# Sheet1.net
KiCad netlist of a schematic drawn in Altium Designer
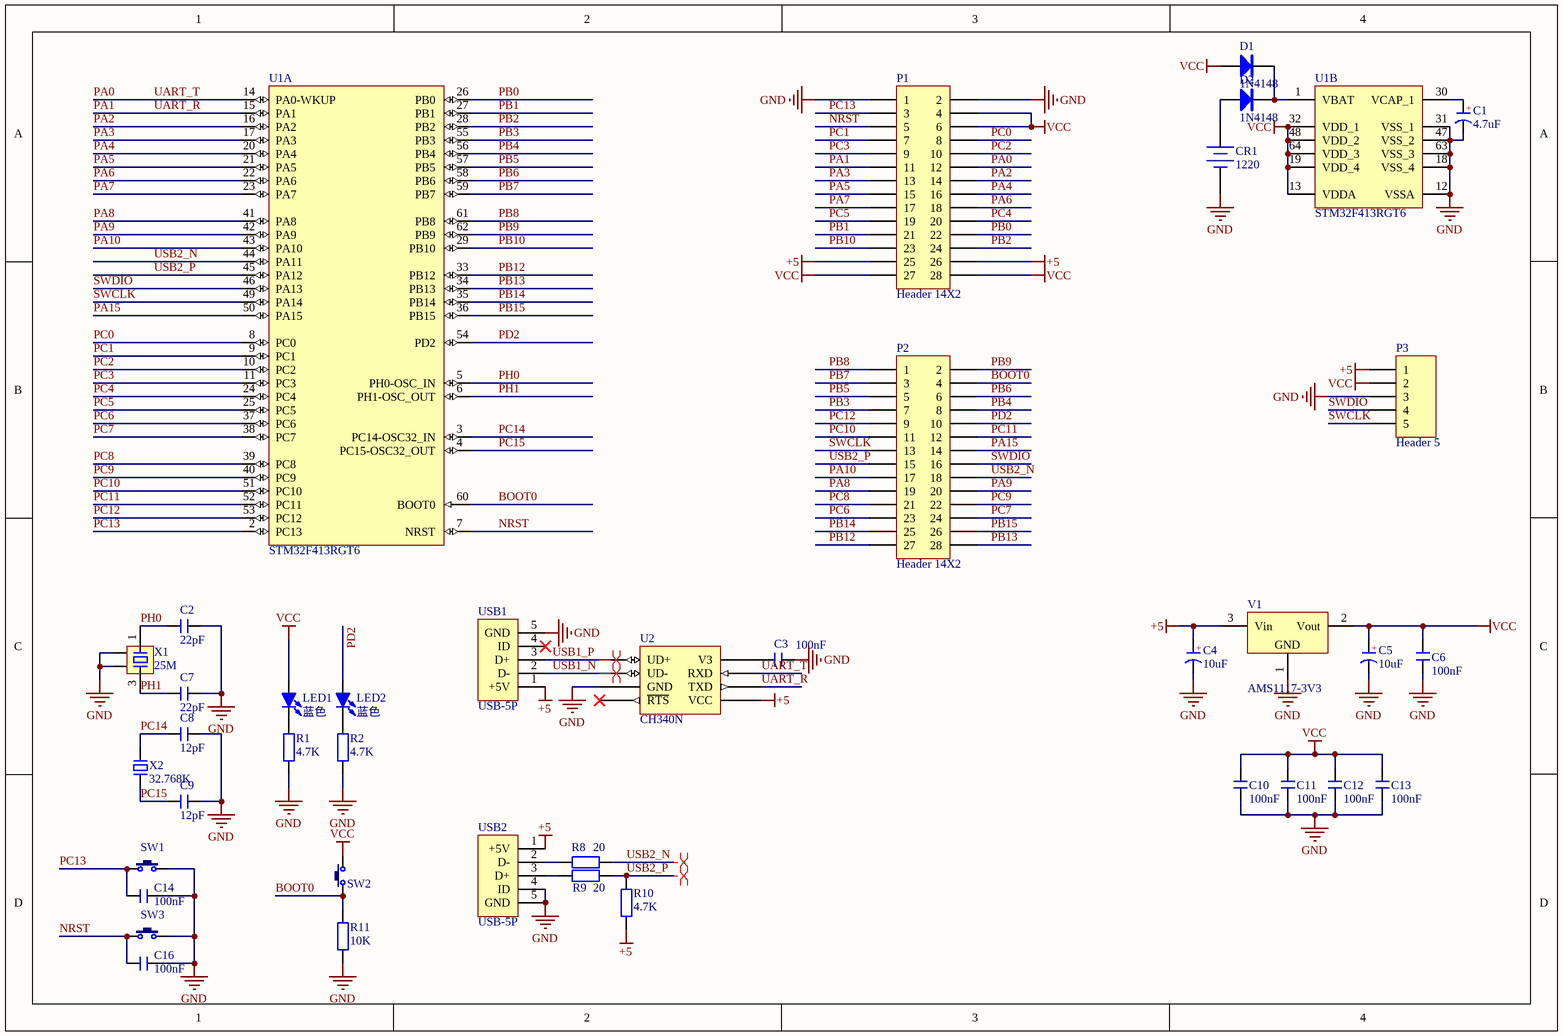
[diagram p0: Sheet1.SchDoc]

(export (version "E")
  (design (tool "Eeschema 10.0.6"))
  (components
    (comp (ref "C1")
      (value "4.7uF")
      (footprint "CD A(3216)")
      (description "贴片钽电容")
      (libsource (lib "Full") (part "CT"))
    )
    (comp (ref "C2")
      (value "22pF")
      (footprint "C 0603_L")
      (description "贴片电容")
      (libsource (lib "Full") (part "C"))
    )
    (comp (ref "C3")
      (value "100nF")
      (footprint "C 0603_L")
      (description "贴片电容")
      (libsource (lib "Full") (part "C"))
    )
    (comp (ref "C4")
      (value "10uF")
      (footprint "CD A(3216)")
      (description "贴片钽电容")
      (libsource (lib "Full") (part "CT"))
    )
    (comp (ref "C5")
      (value "10uF")
      (footprint "CD A(3216)")
      (description "贴片钽电容")
      (libsource (lib "Full") (part "CT"))
    )
    (comp (ref "C6")
      (value "100nF")
      (footprint "C 0603_L")
      (description "贴片电容")
      (libsource (lib "Full") (part "C"))
    )
    (comp (ref "C7")
      (value "22pF")
      (footprint "C 0603_L")
      (description "贴片电容")
      (libsource (lib "Full") (part "C"))
    )
    (comp (ref "C8")
      (value "12pF")
      (footprint "C 0603_L")
      (description "贴片电容")
      (libsource (lib "Full") (part "C"))
    )
    (comp (ref "C9")
      (value "12pF")
      (footprint "C 0603_L")
      (description "贴片电容")
      (libsource (lib "Full") (part "C"))
    )
    (comp (ref "C10")
      (value "100nF")
      (footprint "C 0603_L")
      (description "贴片电容")
      (libsource (lib "Full") (part "C"))
    )
    (comp (ref "C11")
      (value "100nF")
      (footprint "C 0603_L")
      (description "贴片电容")
      (libsource (lib "Full") (part "C"))
    )
    (comp (ref "C12")
      (value "100nF")
      (footprint "C 0603_L")
      (description "贴片电容")
      (libsource (lib "Full") (part "C"))
    )
    (comp (ref "C13")
      (value "100nF")
      (footprint "C 0603_L")
      (description "贴片电容")
      (libsource (lib "Full") (part "C"))
    )
    (comp (ref "C14")
      (value "100nF")
      (footprint "C 0603_L")
      (description "贴片电容")
      (libsource (lib "Full") (part "C"))
    )
    (comp (ref "C16")
      (value "100nF")
      (footprint "C 0603_L")
      (description "贴片电容")
      (libsource (lib "Full") (part "C"))
    )
    (comp (ref "CR1")
      (value "1220")
      (footprint "CR1220_B")
      (description "微型电池")
      (fields (field (name "版权归属") "封装库来自淘宝 ID：黄晶宝石"))
      (libsource (lib "Full") (part "CR-3V"))
    )
    (comp (ref "D1")
      (value "1N4148")
      (footprint "SOD-323")
      (description "开关二极管")
      (libsource (lib "Full") (part "1N4148"))
    )
    (comp (ref "D2")
      (value "1N4148")
      (footprint "SOD-323")
      (description "开关二极管")
      (libsource (lib "Full") (part "1N4148"))
    )
    (comp (ref "LED1")
      (value "蓝色")
      (footprint "LED 0805B")
      (description "贴片LED")
      (fields (field (name "版权归属") "封装库来自淘宝 ID：黄晶宝石"))
      (libsource (lib "Full") (part "LED-SMD"))
    )
    (comp (ref "LED2")
      (value "蓝色")
      (footprint "LED 0805B")
      (description "贴片LED")
      (fields (field (name "版权归属") "封装库来自淘宝 ID：黄晶宝石"))
      (libsource (lib "Full") (part "LED-SMD"))
    )
    (comp (ref "P1")
      (value "Header 14X2")
      (footprint "HDR2X14")
      (description "Header, 14-Pin, Dual row")
      (fields (field (name "PUBLISHER") "Altium Limited"))
      (libsource (lib "Miscellaneous Connectors") (part "Header 14X2"))
    )
    (comp (ref "P2")
      (value "Header 14X2")
      (footprint "HDR2X14")
      (description "Header, 14-Pin, Dual row")
      (fields (field (name "PUBLISHER") "Altium Limited"))
      (libsource (lib "Miscellaneous Connectors") (part "Header 14X2"))
    )
    (comp (ref "P3")
      (value "Header 5")
      (footprint "HDR1X5")
      (description "Header, 5-Pin")
      (fields (field (name "PUBLISHER") "Altium Limited"))
      (libsource (lib "Miscellaneous Connectors") (part "Header 5"))
    )
    (comp (ref "R1")
      (value "4.7K")
      (footprint "R 0603_L")
      (description "贴片电阻")
      (fields (field (name "版权归属") "来自淘宝 ID：黄晶宝石"))
      (libsource (lib "Full") (part "R"))
    )
    (comp (ref "R2")
      (value "4.7K")
      (footprint "R 0603_L")
      (description "贴片电阻")
      (fields (field (name "版权归属") "来自淘宝 ID：黄晶宝石"))
      (libsource (lib "Full") (part "R"))
    )
    (comp (ref "R8")
      (value "20")
      (footprint "R 0603_L")
      (description "贴片电阻")
      (fields (field (name "版权归属") "来自淘宝 ID：黄晶宝石"))
      (libsource (lib "Full") (part "R"))
    )
    (comp (ref "R9")
      (value "20")
      (footprint "R 0603_L")
      (description "贴片电阻")
      (fields (field (name "版权归属") "来自淘宝 ID：黄晶宝石"))
      (libsource (lib "Full") (part "R"))
    )
    (comp (ref "R10")
      (value "4.7K")
      (footprint "R 0603_L")
      (description "贴片电阻")
      (fields (field (name "版权归属") "来自淘宝 ID：黄晶宝石"))
      (libsource (lib "Full") (part "R"))
    )
    (comp (ref "R11")
      (value "10K")
      (footprint "R 0603_L")
      (description "贴片电阻")
      (fields (field (name "版权归属") "来自淘宝 ID：黄晶宝石"))
      (libsource (lib "Full") (part "R"))
    )
    (comp (ref "SW1")
      (value "3x6x5")
      (footprint "TSW SMD-3*6*2.5")
      (description "3x6轻触开关")
      (fields (field (name "版权归属") "封装库来自淘宝 ID：黄晶宝石"))
      (libsource (lib "") (part "TSW 3x6_1"))
    )
    (comp (ref "SW2")
      (value "3x6x5")
      (footprint "TSW SMD-3*6*2.5")
      (description "3x6轻触开关")
      (fields (field (name "版权归属") "封装库来自淘宝 ID：黄晶宝石"))
      (libsource (lib "Full") (part "TSW 3x6"))
    )
    (comp (ref "SW3")
      (value "3x6x5")
      (footprint "TSW SMD-3*6*2.5")
      (description "3x6轻触开关")
      (fields (field (name "版权归属") "封装库来自淘宝 ID：黄晶宝石"))
      (libsource (lib "") (part "TSW 3x6_1"))
    )
    (comp (ref "U1")
      (value "STM32F413RGT6")
      (footprint "STM-LQFP64_N")
      (fields (field (name "PARTNUMBER") "STM32F103RCT6"))
      (libsource (lib "Schlib1") (part "STM32F413RGT6"))
    )
    (comp (ref "U2")
      (value "CH340N")
      (footprint "SOP8")
      (description "SOP8封装USB转串口芯片")
      (libsource (lib "MyLib") (part "CH340N"))
    )
    (comp (ref "USB1")
      (value "USB-5P")
      (footprint "USB-MICRO")
      (description "微型USB母座")
      (libsource (lib "") (part "USB-5P_1"))
    )
    (comp (ref "USB2")
      (value "USB-5P")
      (footprint "USB-MICRO")
      (description "微型USB母座")
      (libsource (lib "Full") (part "USB-5P"))
    )
    (comp (ref "V1")
      (value "AMS1117-3V3")
      (footprint "SOT223_L")
      (description "三端稳压芯片")
      (libsource (lib "Full") (part "AMS1117"))
    )
    (comp (ref "X1")
      (value "25M")
      (footprint "OSC 3225-4P")
      (description "4脚无源晶振")
      (fields (field (name "版权归属") "封装库来自淘宝卖家 ID：黄晶宝石"))
      (libsource (lib "Full") (part "XTAL-4P"))
    )
    (comp (ref "X2")
      (value "32.768K")
      (footprint "OSC 3215-2P")
      (description "2脚无源脚晶振")
      (fields (field (name "版权归属") "封装库来自淘宝卖家 ID：黄晶宝石"))
      (libsource (lib "Full") (part "XTAL-2P"))
    )
  )
  (nets
    (net (code "1") (name "+5") (class "Default")
      (node (ref "C4") (pin "1") (pinfunction "A_1") (pintype "passive"))
      (node (ref "P1") (pin "25") (pinfunction "25_25") (pintype "passive"))
      (node (ref "P1") (pin "26") (pinfunction "26_26") (pintype "passive"))
      (node (ref "P3") (pin "1") (pinfunction "1_1") (pintype "passive"))
      (node (ref "R10") (pin "1") (pinfunction "1_1") (pintype "passive"))
      (node (ref "U2") (pin "5") (pinfunction "VCC_5") (pintype "power_in"))
      (node (ref "USB1") (pin "1") (pinfunction "+5V_1") (pintype "passive"))
      (node (ref "USB2") (pin "1") (pinfunction "+5V_1") (pintype "passive"))
      (node (ref "V1") (pin "3") (pinfunction "Vin_3") (pintype "passive"))
    )
    (net (code "2") (name "/BOOT0") (class "Default")
      (node (ref "P2") (pin "4") (pinfunction "4_4") (pintype "passive"))
      (node (ref "R11") (pin "2") (pinfunction "2_2") (pintype "passive"))
      (node (ref "SW2") (pin "1") (pinfunction "1_1") (pintype "passive"))
      (node (ref "U1") (pin "60") (pinfunction "BOOT0_60") (pintype "input"))
    )
    (net (code "3") (name "/NRST") (class "Default")
      (node (ref "C16") (pin "1") (pinfunction "1_1") (pintype "passive"))
      (node (ref "P1") (pin "5") (pinfunction "5_5") (pintype "passive"))
      (node (ref "SW3") (pin "1") (pinfunction "1_1") (pintype "passive"))
      (node (ref "U1") (pin "7") (pinfunction "NRST_7") (pintype "bidirectional"))
    )
    (net (code "4") (name "/PA0") (class "Default")
      (node (ref "P1") (pin "12") (pinfunction "12_12") (pintype "passive"))
      (node (ref "U1") (pin "14") (pinfunction "PA0-WKUP_14") (pintype "bidirectional"))
      (node (ref "U2") (pin "7") (pinfunction "RXD_7") (pintype "input"))
    )
    (net (code "5") (name "/PA1") (class "Default")
      (node (ref "P1") (pin "11") (pinfunction "11_11") (pintype "passive"))
      (node (ref "U1") (pin "15") (pinfunction "PA1_15") (pintype "bidirectional"))
      (node (ref "U2") (pin "6") (pinfunction "TXD_6") (pintype "output"))
    )
    (net (code "6") (name "/PA2") (class "Default")
      (node (ref "P1") (pin "14") (pinfunction "14_14") (pintype "passive"))
      (node (ref "U1") (pin "16") (pinfunction "PA2_16") (pintype "bidirectional"))
    )
    (net (code "7") (name "/PA3") (class "Default")
      (node (ref "P1") (pin "13") (pinfunction "13_13") (pintype "passive"))
      (node (ref "U1") (pin "17") (pinfunction "PA3_17") (pintype "bidirectional"))
    )
    (net (code "8") (name "/PA4") (class "Default")
      (node (ref "P1") (pin "16") (pinfunction "16_16") (pintype "passive"))
      (node (ref "U1") (pin "20") (pinfunction "PA4_20") (pintype "bidirectional"))
    )
    (net (code "9") (name "/PA5") (class "Default")
      (node (ref "P1") (pin "15") (pinfunction "15_15") (pintype "passive"))
      (node (ref "U1") (pin "21") (pinfunction "PA5_21") (pintype "bidirectional"))
    )
    (net (code "10") (name "/PA6") (class "Default")
      (node (ref "P1") (pin "18") (pinfunction "18_18") (pintype "passive"))
      (node (ref "U1") (pin "22") (pinfunction "PA6_22") (pintype "bidirectional"))
    )
    (net (code "11") (name "/PA7") (class "Default")
      (node (ref "P1") (pin "17") (pinfunction "17_17") (pintype "passive"))
      (node (ref "U1") (pin "23") (pinfunction "PA7_23") (pintype "bidirectional"))
    )
    (net (code "12") (name "/PA8") (class "Default")
      (node (ref "P2") (pin "19") (pinfunction "19_19") (pintype "passive"))
      (node (ref "U1") (pin "41") (pinfunction "PA8_41") (pintype "bidirectional"))
    )
    (net (code "13") (name "/PA9") (class "Default")
      (node (ref "P2") (pin "20") (pinfunction "20_20") (pintype "passive"))
      (node (ref "U1") (pin "42") (pinfunction "PA9_42") (pintype "bidirectional"))
    )
    (net (code "14") (name "/PA10") (class "Default")
      (node (ref "P2") (pin "17") (pinfunction "17_17") (pintype "passive"))
      (node (ref "U1") (pin "43") (pinfunction "PA10_43") (pintype "bidirectional"))
    )
    (net (code "15") (name "/PA15") (class "Default")
      (node (ref "P2") (pin "14") (pinfunction "14_14") (pintype "passive"))
      (node (ref "U1") (pin "50") (pinfunction "PA15_50") (pintype "bidirectional"))
    )
    (net (code "16") (name "/PB0") (class "Default")
      (node (ref "P1") (pin "22") (pinfunction "22_22") (pintype "passive"))
      (node (ref "U1") (pin "26") (pinfunction "PB0_26") (pintype "bidirectional"))
    )
    (net (code "17") (name "/PB1") (class "Default")
      (node (ref "P1") (pin "21") (pinfunction "21_21") (pintype "passive"))
      (node (ref "U1") (pin "27") (pinfunction "PB1_27") (pintype "bidirectional"))
    )
    (net (code "18") (name "/PB2") (class "Default")
      (node (ref "P1") (pin "24") (pinfunction "24_24") (pintype "passive"))
      (node (ref "U1") (pin "28") (pinfunction "PB2_28") (pintype "bidirectional"))
    )
    (net (code "19") (name "/PB3") (class "Default")
      (node (ref "P2") (pin "7") (pinfunction "7_7") (pintype "passive"))
      (node (ref "U1") (pin "55") (pinfunction "PB3_55") (pintype "bidirectional"))
    )
    (net (code "20") (name "/PB4") (class "Default")
      (node (ref "P2") (pin "8") (pinfunction "8_8") (pintype "passive"))
      (node (ref "U1") (pin "56") (pinfunction "PB4_56") (pintype "bidirectional"))
    )
    (net (code "21") (name "/PB5") (class "Default")
      (node (ref "P2") (pin "5") (pinfunction "5_5") (pintype "passive"))
      (node (ref "U1") (pin "57") (pinfunction "PB5_57") (pintype "bidirectional"))
    )
    (net (code "22") (name "/PB6") (class "Default")
      (node (ref "P2") (pin "6") (pinfunction "6_6") (pintype "passive"))
      (node (ref "U1") (pin "58") (pinfunction "PB6_58") (pintype "bidirectional"))
    )
    (net (code "23") (name "/PB7") (class "Default")
      (node (ref "P2") (pin "3") (pinfunction "3_3") (pintype "passive"))
      (node (ref "U1") (pin "59") (pinfunction "PB7_59") (pintype "bidirectional"))
    )
    (net (code "24") (name "/PB8") (class "Default")
      (node (ref "P2") (pin "1") (pinfunction "1_1") (pintype "passive"))
      (node (ref "U1") (pin "61") (pinfunction "PB8_61") (pintype "bidirectional"))
    )
    (net (code "25") (name "/PB9") (class "Default")
      (node (ref "P2") (pin "2") (pinfunction "2_2") (pintype "passive"))
      (node (ref "U1") (pin "62") (pinfunction "PB9_62") (pintype "bidirectional"))
    )
    (net (code "26") (name "/PB10") (class "Default")
      (node (ref "P1") (pin "23") (pinfunction "23_23") (pintype "passive"))
      (node (ref "U1") (pin "29") (pinfunction "PB10_29") (pintype "bidirectional"))
    )
    (net (code "27") (name "/PB12") (class "Default")
      (node (ref "P2") (pin "27") (pinfunction "27_27") (pintype "passive"))
      (node (ref "U1") (pin "33") (pinfunction "PB12_33") (pintype "bidirectional"))
    )
    (net (code "28") (name "/PB13") (class "Default")
      (node (ref "P2") (pin "28") (pinfunction "28_28") (pintype "passive"))
      (node (ref "U1") (pin "34") (pinfunction "PB13_34") (pintype "bidirectional"))
    )
    (net (code "29") (name "/PB14") (class "Default")
      (node (ref "P2") (pin "25") (pinfunction "25_25") (pintype "passive"))
      (node (ref "U1") (pin "35") (pinfunction "PB14_35") (pintype "bidirectional"))
    )
    (net (code "30") (name "/PB15") (class "Default")
      (node (ref "P2") (pin "26") (pinfunction "26_26") (pintype "passive"))
      (node (ref "U1") (pin "36") (pinfunction "PB15_36") (pintype "bidirectional"))
    )
    (net (code "31") (name "/PC0") (class "Default")
      (node (ref "P1") (pin "8") (pinfunction "8_8") (pintype "passive"))
      (node (ref "U1") (pin "8") (pinfunction "PC0_8") (pintype "bidirectional"))
    )
    (net (code "32") (name "/PC1") (class "Default")
      (node (ref "P1") (pin "7") (pinfunction "7_7") (pintype "passive"))
      (node (ref "U1") (pin "9") (pinfunction "PC1_9") (pintype "bidirectional"))
    )
    (net (code "33") (name "/PC2") (class "Default")
      (node (ref "P1") (pin "10") (pinfunction "10_10") (pintype "passive"))
      (node (ref "U1") (pin "10") (pinfunction "PC2_10") (pintype "bidirectional"))
    )
    (net (code "34") (name "/PC3") (class "Default")
      (node (ref "P1") (pin "9") (pinfunction "9_9") (pintype "passive"))
      (node (ref "U1") (pin "11") (pinfunction "PC3_11") (pintype "bidirectional"))
    )
    (net (code "35") (name "/PC4") (class "Default")
      (node (ref "P1") (pin "20") (pinfunction "20_20") (pintype "passive"))
      (node (ref "U1") (pin "24") (pinfunction "PC4_24") (pintype "bidirectional"))
    )
    (net (code "36") (name "/PC5") (class "Default")
      (node (ref "P1") (pin "19") (pinfunction "19_19") (pintype "passive"))
      (node (ref "U1") (pin "25") (pinfunction "PC5_25") (pintype "bidirectional"))
    )
    (net (code "37") (name "/PC6") (class "Default")
      (node (ref "P2") (pin "23") (pinfunction "23_23") (pintype "passive"))
      (node (ref "U1") (pin "37") (pinfunction "PC6_37") (pintype "bidirectional"))
    )
    (net (code "38") (name "/PC7") (class "Default")
      (node (ref "P2") (pin "24") (pinfunction "24_24") (pintype "passive"))
      (node (ref "U1") (pin "38") (pinfunction "PC7_38") (pintype "bidirectional"))
    )
    (net (code "39") (name "/PC8") (class "Default")
      (node (ref "P2") (pin "21") (pinfunction "21_21") (pintype "passive"))
      (node (ref "U1") (pin "39") (pinfunction "PC8_39") (pintype "bidirectional"))
    )
    (net (code "40") (name "/PC9") (class "Default")
      (node (ref "P2") (pin "22") (pinfunction "22_22") (pintype "passive"))
      (node (ref "U1") (pin "40") (pinfunction "PC9_40") (pintype "bidirectional"))
    )
    (net (code "41") (name "/PC10") (class "Default")
      (node (ref "P2") (pin "11") (pinfunction "11_11") (pintype "passive"))
      (node (ref "U1") (pin "51") (pinfunction "PC10_51") (pintype "bidirectional"))
    )
    (net (code "42") (name "/PC11") (class "Default")
      (node (ref "P2") (pin "12") (pinfunction "12_12") (pintype "passive"))
      (node (ref "U1") (pin "52") (pinfunction "PC11_52") (pintype "bidirectional"))
    )
    (net (code "43") (name "/PC12") (class "Default")
      (node (ref "P2") (pin "9") (pinfunction "9_9") (pintype "passive"))
      (node (ref "U1") (pin "53") (pinfunction "PC12_53") (pintype "bidirectional"))
    )
    (net (code "44") (name "/PC13") (class "Default")
      (node (ref "C14") (pin "1") (pinfunction "1_1") (pintype "passive"))
      (node (ref "P1") (pin "3") (pinfunction "3_3") (pintype "passive"))
      (node (ref "SW1") (pin "1") (pinfunction "1_1") (pintype "passive"))
      (node (ref "U1") (pin "2") (pinfunction "PC13_2") (pintype "bidirectional"))
    )
    (net (code "45") (name "/PC14") (class "Default")
      (node (ref "C8") (pin "1") (pinfunction "1_1") (pintype "passive"))
      (node (ref "U1") (pin "3") (pinfunction "PC14-OSC32_IN_3") (pintype "bidirectional"))
      (node (ref "X2") (pin "2") (pinfunction "2_2") (pintype "passive"))
    )
    (net (code "46") (name "/PC15") (class "Default")
      (node (ref "C9") (pin "1") (pinfunction "1_1") (pintype "passive"))
      (node (ref "U1") (pin "4") (pinfunction "PC15-OSC32_OUT_4") (pintype "bidirectional"))
      (node (ref "X2") (pin "1") (pinfunction "1_1") (pintype "passive"))
    )
    (net (code "47") (name "/PD2") (class "Default")
      (node (ref "LED2") (pin "1") (pinfunction "A_1") (pintype "passive"))
      (node (ref "P2") (pin "10") (pinfunction "10_10") (pintype "passive"))
      (node (ref "U1") (pin "54") (pinfunction "PD2_54") (pintype "bidirectional"))
    )
    (net (code "48") (name "/PH0") (class "Default")
      (node (ref "C2") (pin "1") (pinfunction "1_1") (pintype "passive"))
      (node (ref "U1") (pin "5") (pinfunction "PH0-OSC_IN_5") (pintype "bidirectional"))
      (node (ref "X1") (pin "1") (pinfunction "1_1") (pintype "passive"))
    )
    (net (code "49") (name "/PH1") (class "Default")
      (node (ref "C7") (pin "1") (pinfunction "1_1") (pintype "passive"))
      (node (ref "U1") (pin "6") (pinfunction "PH1-OSC_OUT_6") (pintype "bidirectional"))
      (node (ref "X1") (pin "3") (pinfunction "3_3") (pintype "passive"))
    )
    (net (code "50") (name "/SWCLK") (class "Default")
      (node (ref "P2") (pin "13") (pinfunction "13_13") (pintype "passive"))
      (node (ref "P3") (pin "5") (pinfunction "5_5") (pintype "passive"))
      (node (ref "U1") (pin "49") (pinfunction "PA14_49") (pintype "bidirectional"))
    )
    (net (code "51") (name "/SWDIO") (class "Default")
      (node (ref "P2") (pin "16") (pinfunction "16_16") (pintype "passive"))
      (node (ref "P3") (pin "4") (pinfunction "4_4") (pintype "passive"))
      (node (ref "U1") (pin "46") (pinfunction "PA13_46") (pintype "bidirectional"))
    )
    (net (code "52") (name "/USB1_N") (class "Default")
      (node (ref "U2") (pin "2") (pinfunction "UD-_2") (pintype "bidirectional"))
      (node (ref "USB1") (pin "2") (pinfunction "D-_2") (pintype "passive"))
    )
    (net (code "53") (name "/USB1_P") (class "Default")
      (node (ref "U2") (pin "1") (pinfunction "UD+_1") (pintype "bidirectional"))
      (node (ref "USB1") (pin "3") (pinfunction "D+_3") (pintype "passive"))
    )
    (net (code "54") (name "/USB2_N") (class "Default")
      (node (ref "P2") (pin "18") (pinfunction "18_18") (pintype "passive"))
      (node (ref "R8") (pin "1") (pinfunction "1_1") (pintype "passive"))
      (node (ref "U1") (pin "44") (pinfunction "PA11_44") (pintype "bidirectional"))
    )
    (net (code "55") (name "/USB2_P") (class "Default")
      (node (ref "P2") (pin "15") (pinfunction "15_15") (pintype "passive"))
      (node (ref "R10") (pin "2") (pinfunction "2_2") (pintype "passive"))
      (node (ref "R9") (pin "1") (pinfunction "1_1") (pintype "passive"))
      (node (ref "U1") (pin "45") (pinfunction "PA12_45") (pintype "bidirectional"))
    )
    (net (code "56") (name "GND") (class "Default")
      (node (ref "C1") (pin "2") (pinfunction "K_2") (pintype "passive"))
      (node (ref "C10") (pin "1") (pinfunction "1_1") (pintype "passive"))
      (node (ref "C11") (pin "1") (pinfunction "1_1") (pintype "passive"))
      (node (ref "C12") (pin "1") (pinfunction "1_1") (pintype "passive"))
      (node (ref "C13") (pin "1") (pinfunction "1_1") (pintype "passive"))
      (node (ref "C14") (pin "2") (pinfunction "2_2") (pintype "passive"))
      (node (ref "C16") (pin "2") (pinfunction "2_2") (pintype "passive"))
      (node (ref "C2") (pin "2") (pinfunction "2_2") (pintype "passive"))
      (node (ref "C3") (pin "1") (pinfunction "1_1") (pintype "passive"))
      (node (ref "C4") (pin "2") (pinfunction "K_2") (pintype "passive"))
      (node (ref "C5") (pin "2") (pinfunction "K_2") (pintype "passive"))
      (node (ref "C6") (pin "1") (pinfunction "1_1") (pintype "passive"))
      (node (ref "C7") (pin "2") (pinfunction "2_2") (pintype "passive"))
      (node (ref "C8") (pin "2") (pinfunction "2_2") (pintype "passive"))
      (node (ref "C9") (pin "2") (pinfunction "2_2") (pintype "passive"))
      (node (ref "CR1") (pin "2") (pinfunction "DC-_2") (pintype "passive"))
      (node (ref "P1") (pin "1") (pinfunction "1_1") (pintype "passive"))
      (node (ref "P1") (pin "2") (pinfunction "2_2") (pintype "passive"))
      (node (ref "P3") (pin "3") (pinfunction "3_3") (pintype "passive"))
      (node (ref "R1") (pin "1") (pinfunction "1_1") (pintype "passive"))
      (node (ref "R11") (pin "1") (pinfunction "1_1") (pintype "passive"))
      (node (ref "R2") (pin "1") (pinfunction "1_1") (pintype "passive"))
      (node (ref "SW1") (pin "2") (pinfunction "2_2") (pintype "passive"))
      (node (ref "SW3") (pin "2") (pinfunction "2_2") (pintype "passive"))
      (node (ref "U1") (pin "12") (pinfunction "VSSA_12") (pintype "power_in"))
      (node (ref "U1") (pin "18") (pinfunction "VSS_4_18") (pintype "power_in"))
      (node (ref "U1") (pin "31") (pinfunction "VSS_1_31") (pintype "power_in"))
      (node (ref "U1") (pin "47") (pinfunction "VSS_2_47") (pintype "power_in"))
      (node (ref "U1") (pin "63") (pinfunction "VSS_3_63") (pintype "power_in"))
      (node (ref "U2") (pin "3") (pinfunction "GND_3") (pintype "power_in"))
      (node (ref "USB1") (pin "5") (pinfunction "GND_5") (pintype "passive"))
      (node (ref "USB2") (pin "4") (pinfunction "ID_4") (pintype "passive"))
      (node (ref "USB2") (pin "5") (pinfunction "GND_5") (pintype "passive"))
      (node (ref "V1") (pin "1") (pinfunction "GND_1") (pintype "passive"))
      (node (ref "X1") (pin "2") (pinfunction "2_2") (pintype "passive"))
      (node (ref "X1") (pin "4") (pinfunction "4_4") (pintype "passive"))
    )
    (net (code "57") (name "Net-(C1-A)") (class "Default")
      (node (ref "C1") (pin "1") (pinfunction "A_1") (pintype "passive"))
      (node (ref "U1") (pin "30") (pinfunction "VCAP_1_30") (pintype "power_in"))
    )
    (net (code "58") (name "Net-(CR1-DC+)") (class "Default")
      (node (ref "CR1") (pin "1") (pinfunction "DC+_1") (pintype "passive"))
      (node (ref "D2") (pin "1") (pinfunction "A_1") (pintype "passive"))
    )
    (net (code "59") (name "Net-(D1-K)") (class "Default")
      (node (ref "D1") (pin "2") (pinfunction "K_2") (pintype "passive"))
      (node (ref "D2") (pin "2") (pinfunction "K_2") (pintype "passive"))
      (node (ref "U1") (pin "1") (pinfunction "VBAT_1") (pintype "power_in"))
    )
    (net (code "60") (name "Net-(LED1-K)") (class "Default")
      (node (ref "LED1") (pin "2") (pinfunction "K_2") (pintype "passive"))
      (node (ref "R1") (pin "2") (pinfunction "2_2") (pintype "passive"))
    )
    (net (code "61") (name "Net-(LED2-K)") (class "Default")
      (node (ref "LED2") (pin "2") (pinfunction "K_2") (pintype "passive"))
      (node (ref "R2") (pin "2") (pinfunction "2_2") (pintype "passive"))
    )
    (net (code "62") (name "Net-(U2-V3)") (class "Default")
      (node (ref "C3") (pin "2") (pinfunction "2_2") (pintype "passive"))
      (node (ref "U2") (pin "8") (pinfunction "V3_8") (pintype "power_in"))
    )
    (net (code "63") (name "Net-(USB2-D+)") (class "Default")
      (node (ref "R9") (pin "2") (pinfunction "2_2") (pintype "passive"))
      (node (ref "USB2") (pin "3") (pinfunction "D+_3") (pintype "passive"))
    )
    (net (code "64") (name "Net-(USB2-D-)") (class "Default")
      (node (ref "R8") (pin "2") (pinfunction "2_2") (pintype "passive"))
      (node (ref "USB2") (pin "2") (pinfunction "D-_2") (pintype "passive"))
    )
    (net (code "65") (name "VCC") (class "Default")
      (node (ref "C10") (pin "2") (pinfunction "2_2") (pintype "passive"))
      (node (ref "C11") (pin "2") (pinfunction "2_2") (pintype "passive"))
      (node (ref "C12") (pin "2") (pinfunction "2_2") (pintype "passive"))
      (node (ref "C13") (pin "2") (pinfunction "2_2") (pintype "passive"))
      (node (ref "C5") (pin "1") (pinfunction "A_1") (pintype "passive"))
      (node (ref "C6") (pin "2") (pinfunction "2_2") (pintype "passive"))
      (node (ref "D1") (pin "1") (pinfunction "A_1") (pintype "passive"))
      (node (ref "LED1") (pin "1") (pinfunction "A_1") (pintype "passive"))
      (node (ref "P1") (pin "27") (pinfunction "27_27") (pintype "passive"))
      (node (ref "P1") (pin "28") (pinfunction "28_28") (pintype "passive"))
      (node (ref "P1") (pin "4") (pinfunction "4_4") (pintype "passive"))
      (node (ref "P1") (pin "6") (pinfunction "6_6") (pintype "passive"))
      (node (ref "P3") (pin "2") (pinfunction "2_2") (pintype "passive"))
      (node (ref "SW2") (pin "2") (pinfunction "2_2") (pintype "passive"))
      (node (ref "U1") (pin "13") (pinfunction "VDDA_13") (pintype "power_in"))
      (node (ref "U1") (pin "19") (pinfunction "VDD_4_19") (pintype "power_in"))
      (node (ref "U1") (pin "32") (pinfunction "VDD_1_32") (pintype "power_in"))
      (node (ref "U1") (pin "48") (pinfunction "VDD_2_48") (pintype "power_in"))
      (node (ref "U1") (pin "64") (pinfunction "VDD_3_64") (pintype "power_in"))
      (node (ref "V1") (pin "2") (pinfunction "Vout_2") (pintype "passive"))
    )
    (net (code "66") (name "unconnected-(U2-~{RTS}-Pad4)") (class "Default")
      (node (ref "U2") (pin "4") (pinfunction "~{RTS}_4") (pintype "output+no_connect"))
    )
    (net (code "67") (name "unconnected-(USB1-ID-Pad4)") (class "Default")
      (node (ref "USB1") (pin "4") (pinfunction "ID_4") (pintype "passive+no_connect"))
    )
  )
)
